# ServoControl.net
KiCad netlist of a schematic drawn in EasyEDA
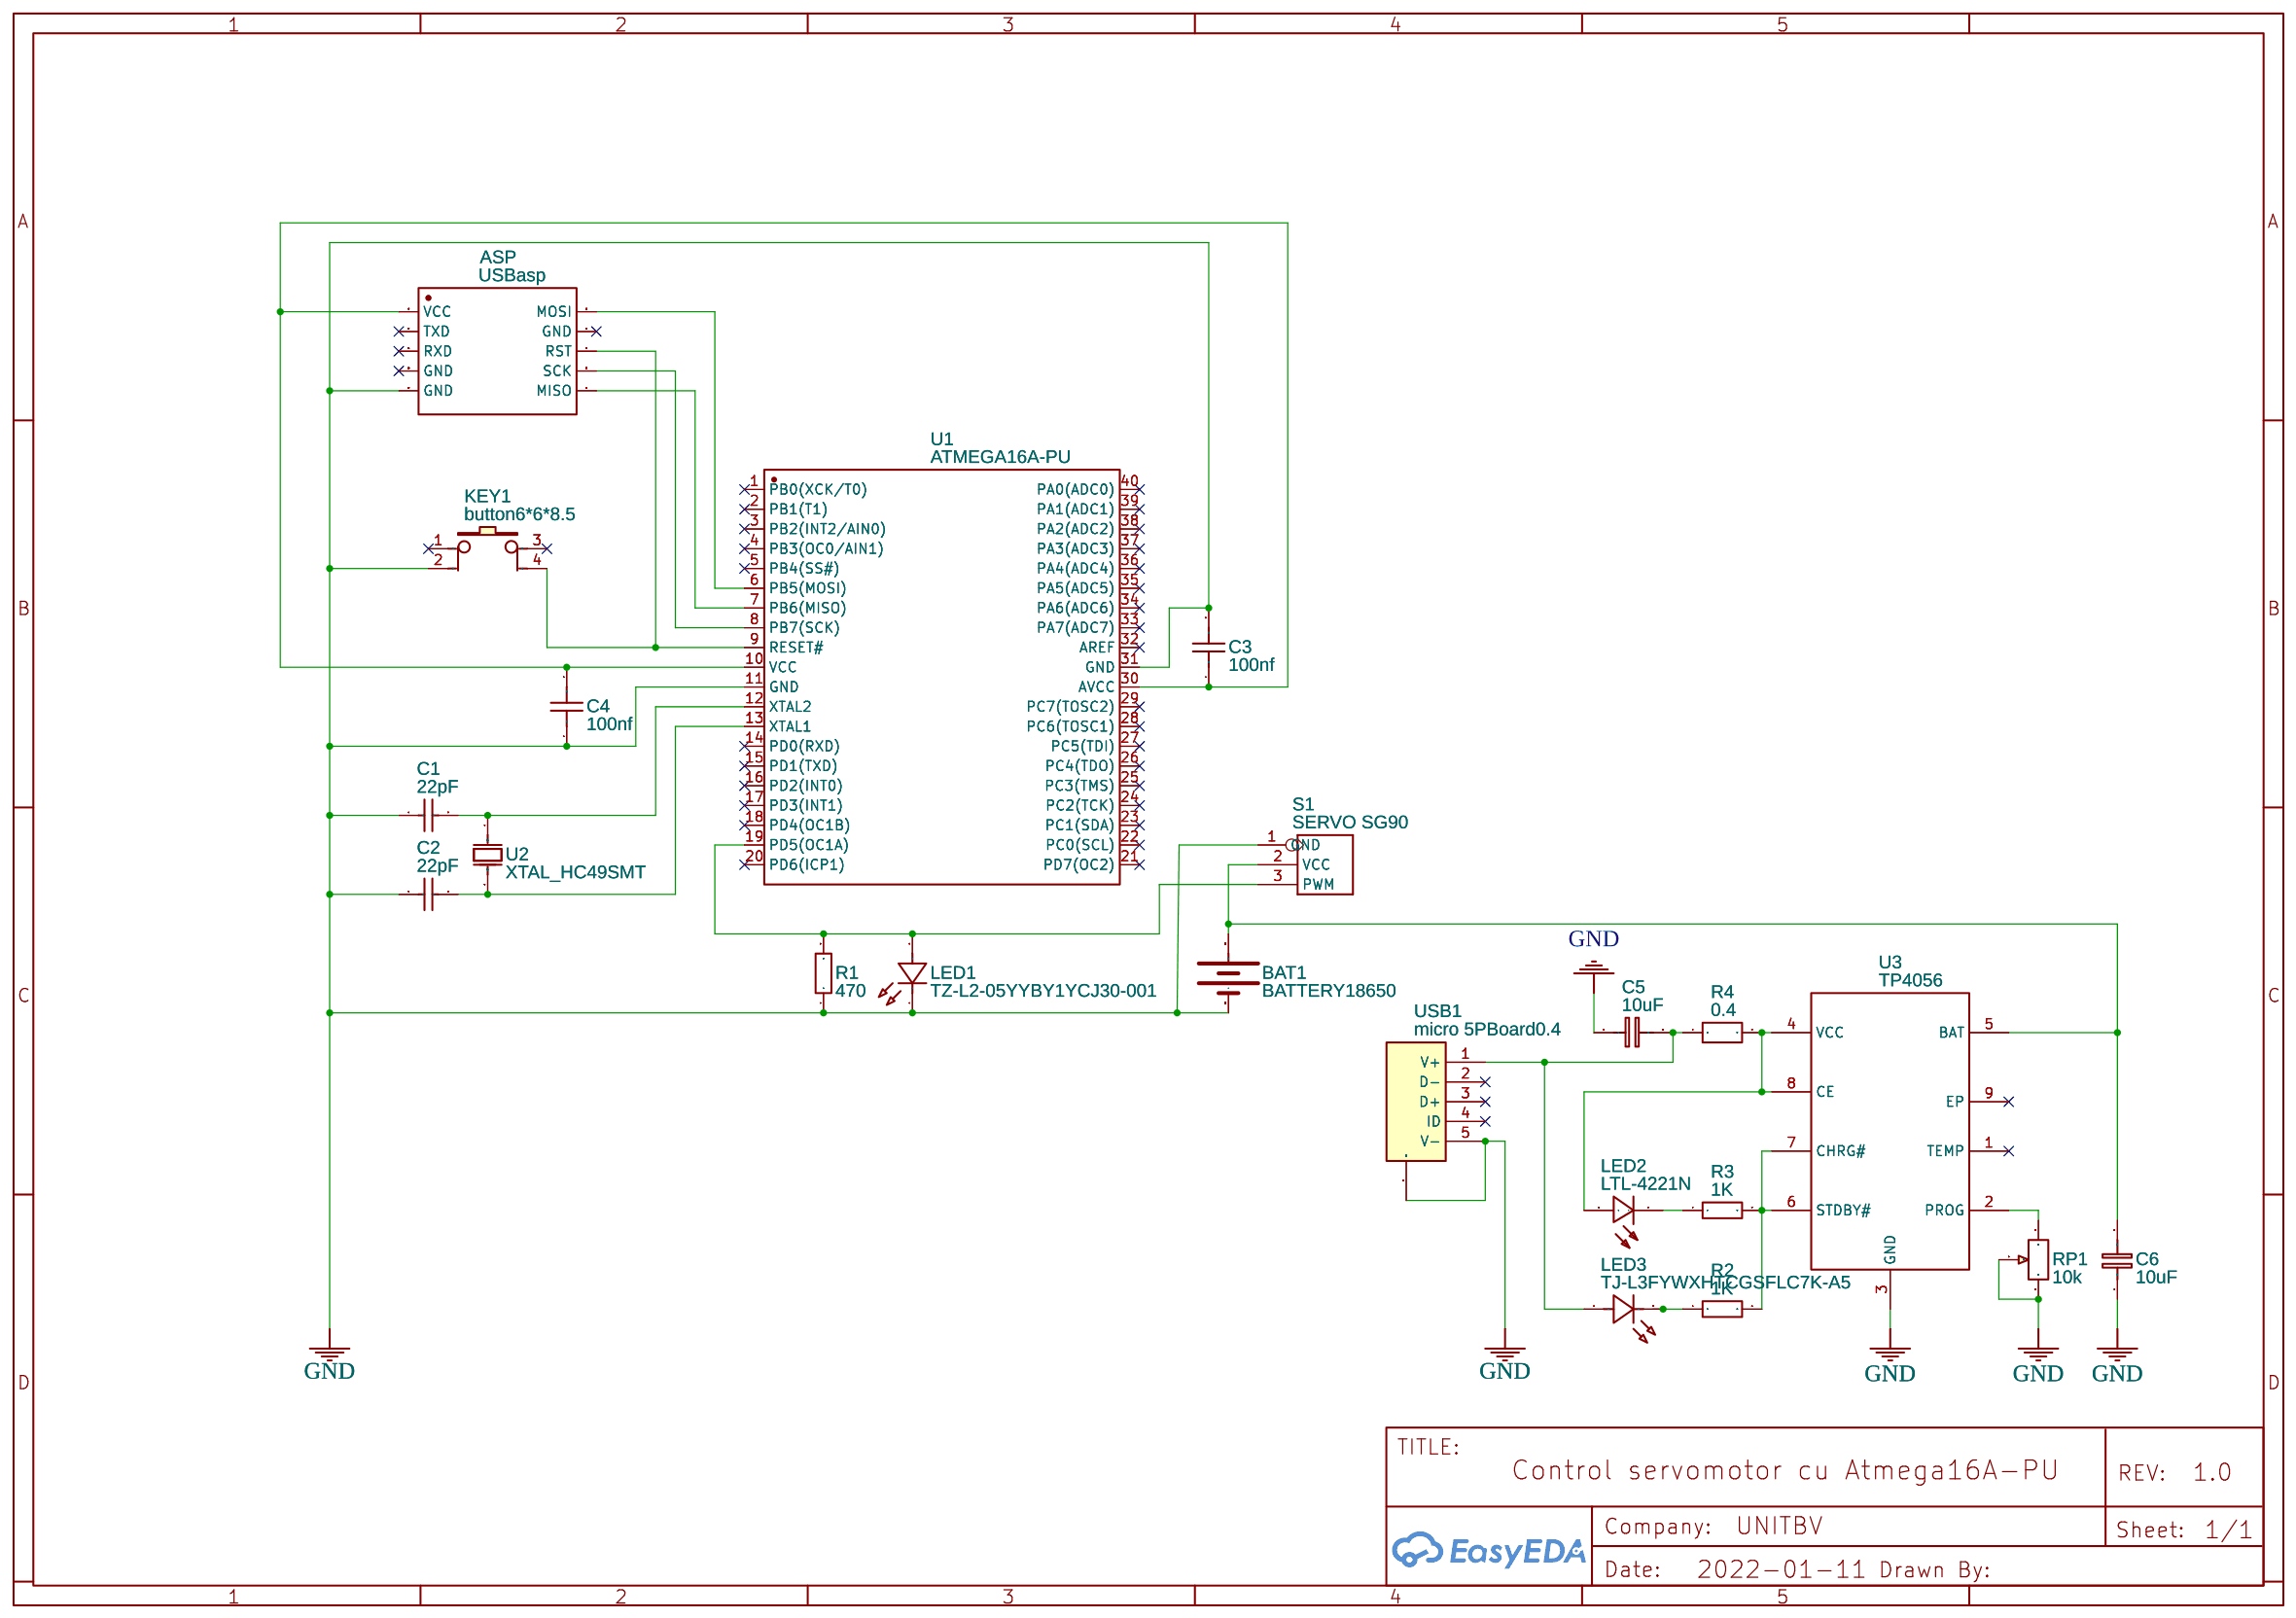
[diagram p0: schematic sheet]

(export (version "E")
  (design (tool "Eeschema 10.0.6"))
  (components
    (comp (ref "ASP") (value "USBasp") (libsource (lib "") (part "USBasp")))
    (comp (ref "BAT1") (value "BATTERY18650") (libsource (lib "") (part "BATTERY18650")))
    (comp (ref "C1")
      (value "22pF")
      (fields
        (field (name "BOM_Manufacturer Part") "22pf/50V 10%")
        (field (name "BOM_Supplier Part") "C9316")
      )
      (libsource (lib "") (part "22pf/50V 10%"))
    )
    (comp (ref "C2")
      (value "22pF")
      (fields
        (field (name "BOM_Manufacturer Part") "22pf/50V 10%")
        (field (name "BOM_Supplier Part") "C9316")
      )
      (libsource (lib "") (part "22pf/50V 10%"))
    )
    (comp (ref "C3")
      (value "100nf")
      (fields
        (field (name "BOM_Manufacturer Part") "Ceramic capacitors47PF 3KV")
        (field (name "BOM_Supplier Part") "C19375")
      )
      (libsource (lib "") (part "CERAMIC CAPACITOR 100NF 50V LEADED"))
    )
    (comp (ref "C4")
      (value "100nf")
      (fields
        (field (name "BOM_Manufacturer Part") "Ceramic capacitors47PF 3KV")
        (field (name "BOM_Supplier Part") "C19375")
      )
      (libsource (lib "") (part "CERAMIC CAPACITOR 100NF 50V LEADED"))
    )
    (comp (ref "C5") (value "10uF") (libsource (lib "") (part "C_0603_EU")))
    (comp (ref "C6") (value "10uF") (libsource (lib "") (part "C_0603_EU_1")))
    (comp (ref "KEY1")
      (value "button6*6*8.5")
      (fields (field (name "BOM_Supplier Part") "C59980"))
      (libsource (lib "") (part "button6*6*8.5"))
    )
    (comp (ref "LED1")
      (value "TZ-L2-05YYBY1YCJ30-001")
      (fields (field (name "BOM_Supplier Part") "C779441"))
      (libsource (lib "") (part "TZ-L2-05YYBY1YCJ30-001"))
    )
    (comp (ref "LED2")
      (value "LTL-4221N")
      (fields (field (name "BOM_Supplier Part") "C125081"))
      (libsource (lib "") (part "LTL-4221N"))
    )
    (comp (ref "LED3")
      (value "TJ-L3FYWXHTCGSFLC7K-A5")
      (fields (field (name "BOM_Supplier Part") "C331045"))
      (libsource (lib "") (part "TJ-L3FYWXHTCGSFLC7K-A5"))
    )
    (comp (ref "R1")
      (value "470")
      (fields (field (name "BOM_Supplier Part") "C119478"))
      (libsource (lib "") (part "MF1W-470Ω±1% T"))
    )
    (comp (ref "R2")
      (value "1K")
      (fields
        (field (name "BOM_Manufacturer Part") "EWWR0003J1K00T9")
        (field (name "BOM_Supplier Part") "C348856")
      )
      (libsource (lib "") (part "EWWR0003J1K00T9"))
    )
    (comp (ref "R3")
      (value "1K")
      (fields
        (field (name "BOM_Manufacturer Part") "EWWR0003J1K00T9")
        (field (name "BOM_Supplier Part") "C348856")
      )
      (libsource (lib "") (part "EWWR0003J1K00T9"))
    )
    (comp (ref "R4") (value "0.4") (libsource (lib "") (part "R_0603_EU")))
    (comp (ref "RP1") (value "10k") (libsource (lib "") (part "R_3386P_EU")))
    (comp (ref "S1") (value "SERVO SG90") (libsource (lib "") (part "SERVO SG90")))
    (comp (ref "U1")
      (value "ATMEGA16A-PU")
      (fields (field (name "BOM_Supplier Part") "C30504"))
      (libsource (lib "") (part "ATMEGA16A-PU"))
    )
    (comp (ref "U2")
      (value "XTAL_HC49SMT")
      (fields (field (name "BOM_Supplier Part") "C9900001625"))
      (libsource (lib "") (part "XTAL_HC49SMT"))
    )
    (comp (ref "U3")
      (value "TP4056")
      (fields (field (name "BOM_Supplier Part") "C16581"))
      (libsource (lib "") (part "TP4056"))
    )
    (comp (ref "USB1")
      (value "micro 5PBoard0.4")
      (fields
        (field (name "BOM_Manufacturer Part") "micro 5PBoard0.4No column lengthened0.75Plus welding feet")
        (field (name "BOM_Supplier Part") "C40947")
      )
      (libsource (lib "") (part "micro 5PBoard0.4No column lengthened0.75Plus welding feet"))
    )
  )
  (nets
    (net (code "1") (name "GND") (class "Default")
      (node (ref "ASP") (pin "GND1") (pinfunction "GND_GND1") (pintype "unspecified"))
      (node (ref "BAT1") (pin "GND@1") (pinfunction "-_GND@1") (pintype "passive"))
      (node (ref "C1") (pin "1") (pinfunction "1_1") (pintype "input"))
      (node (ref "C2") (pin "1") (pinfunction "1_1") (pintype "input"))
      (node (ref "C3") (pin "2") (pinfunction "2_2") (pintype "input"))
      (node (ref "C4") (pin "1") (pinfunction "1_1") (pintype "input"))
      (node (ref "C5") (pin "1") (pinfunction "1_1") (pintype "unspecified"))
      (node (ref "C6") (pin "1") (pinfunction "1_1") (pintype "unspecified"))
      (node (ref "KEY1") (pin "2") (pinfunction "2_2") (pintype "input"))
      (node (ref "LED1") (pin "1") (pinfunction "-_1") (pintype "unspecified"))
      (node (ref "R1") (pin "1") (pinfunction "1_1") (pintype "unspecified"))
      (node (ref "RP1") (pin "1") (pinfunction "1_1") (pintype "input"))
      (node (ref "RP1") (pin "2") (pinfunction "2_2") (pintype "input"))
      (node (ref "S1") (pin "1") (pinfunction "GND_1") (pintype "unspecified"))
      (node (ref "U1") (pin "11") (pinfunction "GND_11") (pintype "unspecified"))
      (node (ref "U1") (pin "31") (pinfunction "GND_31") (pintype "unspecified"))
      (node (ref "U3") (pin "3") (pinfunction "GND_3") (pintype "unspecified"))
      (node (ref "USB1") (pin "0") (pinfunction "MTN6_0") (pintype "input"))
      (node (ref "USB1") (pin "5") (pinfunction "V-_5") (pintype "unspecified"))
    )
    (net (code "2") (name "Net-(BAT1-+)") (class "Default")
      (node (ref "BAT1") (pin "PWR@1") (pinfunction "+_PWR@1") (pintype "passive"))
      (node (ref "C6") (pin "2") (pinfunction "2_2") (pintype "unspecified"))
      (node (ref "S1") (pin "2") (pinfunction "VCC_2") (pintype "unspecified"))
      (node (ref "U3") (pin "5") (pinfunction "BAT_5") (pintype "unspecified"))
    )
    (net (code "3") (name "Net-(LED1-+)") (class "Default")
      (node (ref "LED1") (pin "2") (pinfunction "+_2") (pintype "unspecified"))
      (node (ref "R1") (pin "2") (pinfunction "2_2") (pintype "unspecified"))
      (node (ref "S1") (pin "3") (pinfunction "PWM_3") (pintype "unspecified"))
      (node (ref "U1") (pin "19") (pinfunction "PD5(OC1A)_19") (pintype "unspecified"))
    )
    (net (code "4") (name "Net-(LED2-+)") (class "Default")
      (node (ref "LED2") (pin "2") (pinfunction "+_2") (pintype "unspecified"))
      (node (ref "R4") (pin "2") (pinfunction "2_2") (pintype "unspecified"))
      (node (ref "U3") (pin "4") (pinfunction "VCC_4") (pintype "unspecified"))
      (node (ref "U3") (pin "8") (pinfunction "CE_8") (pintype "unspecified"))
    )
    (net (code "5") (name "Net-(LED2--)") (class "Default")
      (node (ref "LED2") (pin "1") (pinfunction "-_1") (pintype "unspecified"))
      (node (ref "R3") (pin "1") (pinfunction "1_1") (pintype "unspecified"))
    )
    (net (code "6") (name "Net-(LED3-+)") (class "Default")
      (node (ref "C5") (pin "2") (pinfunction "2_2") (pintype "unspecified"))
      (node (ref "LED3") (pin "1") (pinfunction "+_1") (pintype "unspecified"))
      (node (ref "R4") (pin "1") (pinfunction "1_1") (pintype "unspecified"))
      (node (ref "USB1") (pin "1") (pinfunction "V+_1") (pintype "unspecified"))
    )
    (net (code "7") (name "Net-(LED3--)") (class "Default")
      (node (ref "LED3") (pin "2") (pinfunction "-_2") (pintype "unspecified"))
      (node (ref "R2") (pin "1") (pinfunction "1_1") (pintype "unspecified"))
    )
    (net (code "8") (name "Net-(U1-AVCC)") (class "Default")
      (node (ref "ASP") (pin "VCC") (pinfunction "VCC_VCC") (pintype "unspecified"))
      (node (ref "C3") (pin "1") (pinfunction "1_1") (pintype "input"))
      (node (ref "C4") (pin "2") (pinfunction "2_2") (pintype "input"))
      (node (ref "U1") (pin "10") (pinfunction "VCC_10") (pintype "unspecified"))
      (node (ref "U1") (pin "30") (pinfunction "AVCC_30") (pintype "unspecified"))
    )
    (net (code "9") (name "Net-(U1-PB5(MOSI))") (class "Default")
      (node (ref "ASP") (pin "MOSI") (pinfunction "MOSI_MOSI") (pintype "unspecified"))
      (node (ref "U1") (pin "6") (pinfunction "PB5(MOSI)_6") (pintype "unspecified"))
    )
    (net (code "10") (name "Net-(U1-PB6(MISO))") (class "Default")
      (node (ref "ASP") (pin "MISO") (pinfunction "MISO_MISO") (pintype "unspecified"))
      (node (ref "U1") (pin "7") (pinfunction "PB6(MISO)_7") (pintype "unspecified"))
    )
    (net (code "11") (name "Net-(U1-PB7(SCK))") (class "Default")
      (node (ref "ASP") (pin "SCK") (pinfunction "SCK_SCK") (pintype "unspecified"))
      (node (ref "U1") (pin "8") (pinfunction "PB7(SCK)_8") (pintype "unspecified"))
    )
    (net (code "12") (name "Net-(U1-RESET#)") (class "Default")
      (node (ref "ASP") (pin "RST") (pinfunction "RST_RST") (pintype "unspecified"))
      (node (ref "KEY1") (pin "4") (pinfunction "4_4") (pintype "input"))
      (node (ref "U1") (pin "9") (pinfunction "RESET#_9") (pintype "unspecified"))
    )
    (net (code "13") (name "Net-(U1-XTAL1)") (class "Default")
      (node (ref "C2") (pin "2") (pinfunction "2_2") (pintype "input"))
      (node (ref "U1") (pin "13") (pinfunction "XTAL1_13") (pintype "unspecified"))
      (node (ref "U2") (pin "2") (pinfunction "OSC2_2") (pintype "input"))
    )
    (net (code "14") (name "Net-(U1-XTAL2)") (class "Default")
      (node (ref "C1") (pin "2") (pinfunction "2_2") (pintype "input"))
      (node (ref "U1") (pin "12") (pinfunction "XTAL2_12") (pintype "unspecified"))
      (node (ref "U2") (pin "1") (pinfunction "OSC1_1") (pintype "input"))
    )
    (net (code "15") (name "Net-(U3-CHRG#)") (class "Default")
      (node (ref "R2") (pin "2") (pinfunction "2_2") (pintype "unspecified"))
      (node (ref "R3") (pin "2") (pinfunction "2_2") (pintype "unspecified"))
      (node (ref "U3") (pin "6") (pinfunction "STDBY#_6") (pintype "unspecified"))
      (node (ref "U3") (pin "7") (pinfunction "CHRG#_7") (pintype "unspecified"))
    )
    (net (code "16") (name "Net-(U3-PROG)") (class "Default")
      (node (ref "RP1") (pin "3") (pinfunction "3_3") (pintype "input"))
      (node (ref "U3") (pin "2") (pinfunction "PROG_2") (pintype "unspecified"))
    )
    (net (code "17") (name "unconnected-(ASP-GND-PadGND2)") (class "Default")
      (node (ref "ASP") (pin "GND2") (pinfunction "GND_GND2") (pintype "unspecified+no_connect"))
    )
    (net (code "18") (name "unconnected-(ASP-GND-PadGND3)") (class "Default")
      (node (ref "ASP") (pin "GND3") (pinfunction "GND_GND3") (pintype "unspecified+no_connect"))
    )
    (net (code "19") (name "unconnected-(ASP-PadRXD)") (class "Default")
      (node (ref "ASP") (pin "RXD") (pinfunction "RXD_RXD") (pintype "unspecified+no_connect"))
    )
    (net (code "20") (name "unconnected-(ASP-PadTXD)") (class "Default")
      (node (ref "ASP") (pin "TXD") (pinfunction "TXD_TXD") (pintype "unspecified+no_connect"))
    )
    (net (code "21") (name "unconnected-(KEY1-Pad1)") (class "Default")
      (node (ref "KEY1") (pin "1") (pinfunction "1_1") (pintype "input+no_connect"))
    )
    (net (code "22") (name "unconnected-(KEY1-Pad3)") (class "Default")
      (node (ref "KEY1") (pin "3") (pinfunction "3_3") (pintype "input+no_connect"))
    )
    (net (code "23") (name "unconnected-(U1-AREF-Pad32)") (class "Default")
      (node (ref "U1") (pin "32") (pinfunction "AREF_32") (pintype "unspecified+no_connect"))
    )
    (net (code "24") (name "unconnected-(U1-PA0(ADC0)-Pad40)") (class "Default")
      (node (ref "U1") (pin "40") (pinfunction "PA0(ADC0)_40") (pintype "unspecified+no_connect"))
    )
    (net (code "25") (name "unconnected-(U1-PA1(ADC1)-Pad39)") (class "Default")
      (node (ref "U1") (pin "39") (pinfunction "PA1(ADC1)_39") (pintype "unspecified+no_connect"))
    )
    (net (code "26") (name "unconnected-(U1-PA2(ADC2)-Pad38)") (class "Default")
      (node (ref "U1") (pin "38") (pinfunction "PA2(ADC2)_38") (pintype "unspecified+no_connect"))
    )
    (net (code "27") (name "unconnected-(U1-PA3(ADC3)-Pad37)") (class "Default")
      (node (ref "U1") (pin "37") (pinfunction "PA3(ADC3)_37") (pintype "unspecified+no_connect"))
    )
    (net (code "28") (name "unconnected-(U1-PA4(ADC4)-Pad36)") (class "Default")
      (node (ref "U1") (pin "36") (pinfunction "PA4(ADC4)_36") (pintype "unspecified+no_connect"))
    )
    (net (code "29") (name "unconnected-(U1-PA5(ADC5)-Pad35)") (class "Default")
      (node (ref "U1") (pin "35") (pinfunction "PA5(ADC5)_35") (pintype "unspecified+no_connect"))
    )
    (net (code "30") (name "unconnected-(U1-PA6(ADC6)-Pad34)") (class "Default")
      (node (ref "U1") (pin "34") (pinfunction "PA6(ADC6)_34") (pintype "unspecified+no_connect"))
    )
    (net (code "31") (name "unconnected-(U1-PA7(ADC7)-Pad33)") (class "Default")
      (node (ref "U1") (pin "33") (pinfunction "PA7(ADC7)_33") (pintype "unspecified+no_connect"))
    )
    (net (code "32") (name "unconnected-(U1-PB0(XCK{slash}T0)-Pad1)") (class "Default")
      (node (ref "U1") (pin "1") (pinfunction "PB0(XCK/T0)_1") (pintype "unspecified+no_connect"))
    )
    (net (code "33") (name "unconnected-(U1-PB1(T1)-Pad2)") (class "Default")
      (node (ref "U1") (pin "2") (pinfunction "PB1(T1)_2") (pintype "unspecified+no_connect"))
    )
    (net (code "34") (name "unconnected-(U1-PB2(INT2{slash}AIN0)-Pad3)") (class "Default")
      (node (ref "U1") (pin "3") (pinfunction "PB2(INT2/AIN0)_3") (pintype "unspecified+no_connect"))
    )
    (net (code "35") (name "unconnected-(U1-PB3(OC0{slash}AIN1)-Pad4)") (class "Default")
      (node (ref "U1") (pin "4") (pinfunction "PB3(OC0/AIN1)_4") (pintype "unspecified+no_connect"))
    )
    (net (code "36") (name "unconnected-(U1-PB4(SS#)-Pad5)") (class "Default")
      (node (ref "U1") (pin "5") (pinfunction "PB4(SS#)_5") (pintype "unspecified+no_connect"))
    )
    (net (code "37") (name "unconnected-(U1-PC0(SCL)-Pad22)") (class "Default")
      (node (ref "U1") (pin "22") (pinfunction "PC0(SCL)_22") (pintype "unspecified+no_connect"))
    )
    (net (code "38") (name "unconnected-(U1-PC1(SDA)-Pad23)") (class "Default")
      (node (ref "U1") (pin "23") (pinfunction "PC1(SDA)_23") (pintype "unspecified+no_connect"))
    )
    (net (code "39") (name "unconnected-(U1-PC2(TCK)-Pad24)") (class "Default")
      (node (ref "U1") (pin "24") (pinfunction "PC2(TCK)_24") (pintype "unspecified+no_connect"))
    )
    (net (code "40") (name "unconnected-(U1-PC3(TMS)-Pad25)") (class "Default")
      (node (ref "U1") (pin "25") (pinfunction "PC3(TMS)_25") (pintype "unspecified+no_connect"))
    )
    (net (code "41") (name "unconnected-(U1-PC4(TDO)-Pad26)") (class "Default")
      (node (ref "U1") (pin "26") (pinfunction "PC4(TDO)_26") (pintype "unspecified+no_connect"))
    )
    (net (code "42") (name "unconnected-(U1-PC5(TDI)-Pad27)") (class "Default")
      (node (ref "U1") (pin "27") (pinfunction "PC5(TDI)_27") (pintype "unspecified+no_connect"))
    )
    (net (code "43") (name "unconnected-(U1-PC6(TOSC1)-Pad28)") (class "Default")
      (node (ref "U1") (pin "28") (pinfunction "PC6(TOSC1)_28") (pintype "unspecified+no_connect"))
    )
    (net (code "44") (name "unconnected-(U1-PC7(TOSC2)-Pad29)") (class "Default")
      (node (ref "U1") (pin "29") (pinfunction "PC7(TOSC2)_29") (pintype "unspecified+no_connect"))
    )
    (net (code "45") (name "unconnected-(U1-PD0(RXD)-Pad14)") (class "Default")
      (node (ref "U1") (pin "14") (pinfunction "PD0(RXD)_14") (pintype "unspecified+no_connect"))
    )
    (net (code "46") (name "unconnected-(U1-PD1(TXD)-Pad15)") (class "Default")
      (node (ref "U1") (pin "15") (pinfunction "PD1(TXD)_15") (pintype "unspecified+no_connect"))
    )
    (net (code "47") (name "unconnected-(U1-PD2(INT0)-Pad16)") (class "Default")
      (node (ref "U1") (pin "16") (pinfunction "PD2(INT0)_16") (pintype "unspecified+no_connect"))
    )
    (net (code "48") (name "unconnected-(U1-PD3(INT1)-Pad17)") (class "Default")
      (node (ref "U1") (pin "17") (pinfunction "PD3(INT1)_17") (pintype "unspecified+no_connect"))
    )
    (net (code "49") (name "unconnected-(U1-PD4(OC1B)-Pad18)") (class "Default")
      (node (ref "U1") (pin "18") (pinfunction "PD4(OC1B)_18") (pintype "unspecified+no_connect"))
    )
    (net (code "50") (name "unconnected-(U1-PD6(ICP1)-Pad20)") (class "Default")
      (node (ref "U1") (pin "20") (pinfunction "PD6(ICP1)_20") (pintype "unspecified+no_connect"))
    )
    (net (code "51") (name "unconnected-(U1-PD7(OC2)-Pad21)") (class "Default")
      (node (ref "U1") (pin "21") (pinfunction "PD7(OC2)_21") (pintype "unspecified+no_connect"))
    )
    (net (code "52") (name "unconnected-(U3-EP-Pad9)") (class "Default")
      (node (ref "U3") (pin "9") (pinfunction "EP_9") (pintype "unspecified+no_connect"))
    )
    (net (code "53") (name "unconnected-(U3-TEMP-Pad1)") (class "Default")
      (node (ref "U3") (pin "1") (pinfunction "TEMP_1") (pintype "unspecified+no_connect"))
    )
    (net (code "54") (name "unconnected-(USB1-D+-Pad3)") (class "Default")
      (node (ref "USB1") (pin "3") (pinfunction "D+_3") (pintype "unspecified+no_connect"))
    )
    (net (code "55") (name "unconnected-(USB1-D--Pad2)") (class "Default")
      (node (ref "USB1") (pin "2") (pinfunction "D-_2") (pintype "unspecified+no_connect"))
    )
    (net (code "56") (name "unconnected-(USB1-ID-Pad4)") (class "Default")
      (node (ref "USB1") (pin "4") (pinfunction "ID_4") (pintype "unspecified+no_connect"))
    )
  )
)
